# adc-analog.net
KiCad netlist of a schematic drawn in Altium Designer
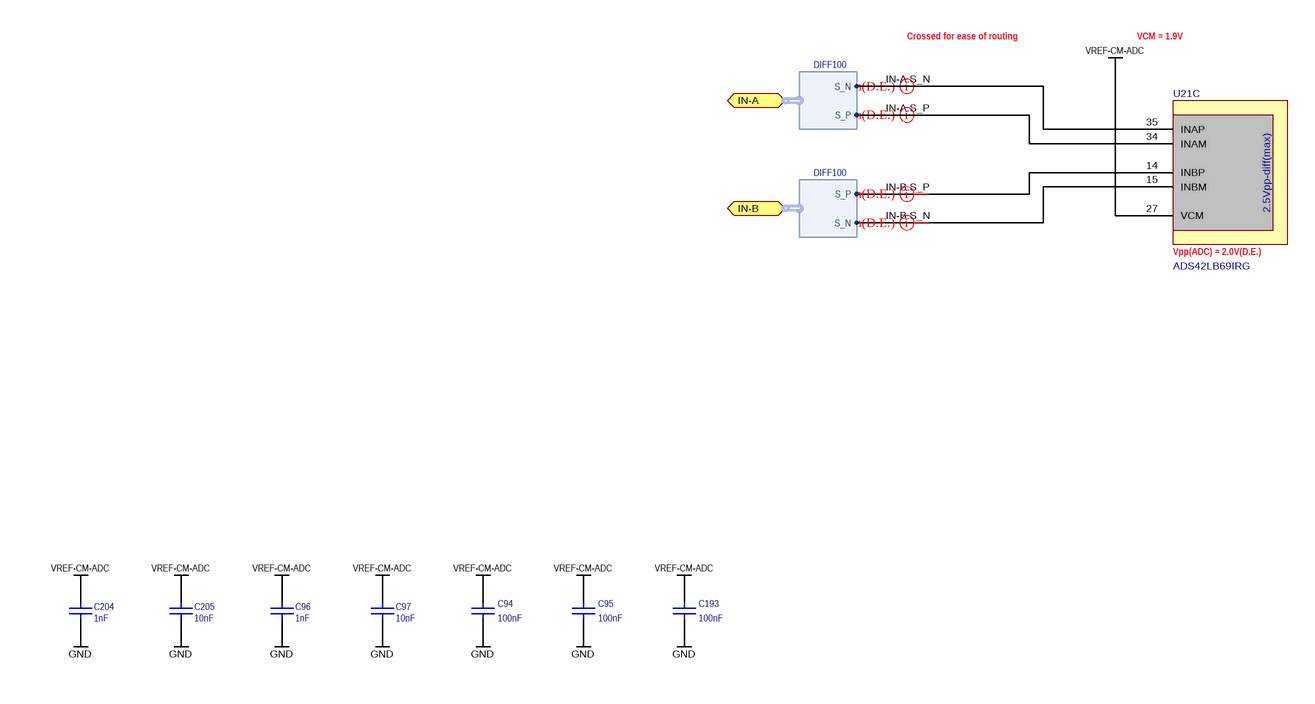
[diagram p0: adc-analog.SchDoc]

(export (version "E")
  (design (tool "Eeschema 10.0.6"))
  (components
    (comp (ref "C94")
      (value "100nF")
      (footprint "CAPC100X50X55L25N")
      (description "Ceramic Capacitor 100nF ±10% 16V X7R 0402")
      (fields (field (name "VOLTAGE") "16V") (field (name "MANUFACTURER") "Murata"))
      (libsource (lib "Graviton") (part "CAP 0402"))
    )
    (comp (ref "C95")
      (value "100nF")
      (footprint "CAPC100X50X55L25N")
      (description "Ceramic Capacitor 100nF ±10% 16V X7R 0402")
      (fields (field (name "VOLTAGE") "16V") (field (name "MANUFACTURER") "Murata"))
      (libsource (lib "Graviton") (part "CAP 0402"))
    )
    (comp (ref "C96")
      (value "1nF")
      (footprint "CAPC100X50X55L25N")
      (description "Ceramic Capacitor 1nF ±5% 50V NP0 0402")
      (fields (field (name "VOLTAGE") "50V") (field (name "MANUFACTURER") "TDK"))
      (libsource (lib "Graviton") (part "CAP 0402"))
    )
    (comp (ref "C97")
      (value "10nF")
      (footprint "CAPC100X50X55L25N")
      (description "Ceramic Capacitor 10nF ±10% 50V X7R 0402")
      (fields (field (name "VOLTAGE") "50V") (field (name "MANUFACTURER") "Murata"))
      (libsource (lib "Graviton") (part "CAP 0402"))
    )
    (comp (ref "C193")
      (value "100nF")
      (footprint "CAPC100X50X55L25N")
      (description "Ceramic Capacitor 100nF ±10% 16V X7R 0402")
      (fields (field (name "VOLTAGE") "16V") (field (name "MANUFACTURER") "Murata"))
      (libsource (lib "Graviton") (part "CAP 0402"))
    )
    (comp (ref "C204")
      (value "1nF")
      (footprint "CAPC100X50X55L25N")
      (description "Ceramic Capacitor 1nF ±5% 50V NP0 0402")
      (fields (field (name "VOLTAGE") "50V") (field (name "MANUFACTURER") "TDK"))
      (libsource (lib "Graviton") (part "CAP 0402"))
    )
    (comp (ref "C205")
      (value "10nF")
      (footprint "CAPC100X50X55L25N")
      (description "Ceramic Capacitor 10nF ±10% 50V X7R 0402")
      (fields (field (name "VOLTAGE") "50V") (field (name "MANUFACTURER") "Murata"))
      (libsource (lib "Graviton") (part "CAP 0402"))
    )
    (comp (ref "U21")
      (value "ADS42LB69IRG")
      (footprint "S-PVQFN-N64")
      (description "Dual-Channel, 16-Bit, 250-MSPS Analog-to-Digital Converter")
      (fields (field (name "MANUFACTURER") "Texas Instruments"))
      (libsource (lib "ti") (part "ADS42LB69IRG"))
    )
  )
  (nets
    (net (code "2") (name "/IN-A.S_N") (class "Default")
      (node (ref "U21") (pin "35") (pinfunction "INAP_35") (pintype "passive"))
    )
    (net (code "3") (name "/IN-A.S_P") (class "Default")
      (node (ref "U21") (pin "34") (pinfunction "INAM_34") (pintype "passive"))
    )
    (net (code "4") (name "/IN-B.S_N") (class "Default")
      (node (ref "U21") (pin "15") (pinfunction "INBM_15") (pintype "passive"))
    )
    (net (code "5") (name "/IN-B.S_P") (class "Default")
      (node (ref "U21") (pin "14") (pinfunction "INBP_14") (pintype "passive"))
    )
    (net (code "7") (name "GND") (class "Default")
      (node (ref "C193") (pin "2") (pinfunction "2_2") (pintype "passive"))
      (node (ref "C204") (pin "1") (pinfunction "1_1") (pintype "passive"))
      (node (ref "C205") (pin "1") (pinfunction "1_1") (pintype "passive"))
      (node (ref "C94") (pin "2") (pinfunction "2_2") (pintype "passive"))
      (node (ref "C95") (pin "2") (pinfunction "2_2") (pintype "passive"))
      (node (ref "C96") (pin "1") (pinfunction "1_1") (pintype "passive"))
      (node (ref "C97") (pin "1") (pinfunction "1_1") (pintype "passive"))
    )
    (net (code "8") (name "VREF-CM-ADC") (class "Default")
      (node (ref "C193") (pin "1") (pinfunction "1_1") (pintype "passive"))
      (node (ref "C204") (pin "2") (pinfunction "2_2") (pintype "passive"))
      (node (ref "C205") (pin "2") (pinfunction "2_2") (pintype "passive"))
      (node (ref "C94") (pin "1") (pinfunction "1_1") (pintype "passive"))
      (node (ref "C95") (pin "1") (pinfunction "1_1") (pintype "passive"))
      (node (ref "C96") (pin "2") (pinfunction "2_2") (pintype "passive"))
      (node (ref "C97") (pin "2") (pinfunction "2_2") (pintype "passive"))
      (node (ref "U21") (pin "27") (pinfunction "VCM_27") (pintype "passive"))
    )
  )
)
